# Relay-Switch.net
KiCad netlist of a schematic drawn in Altium Designer
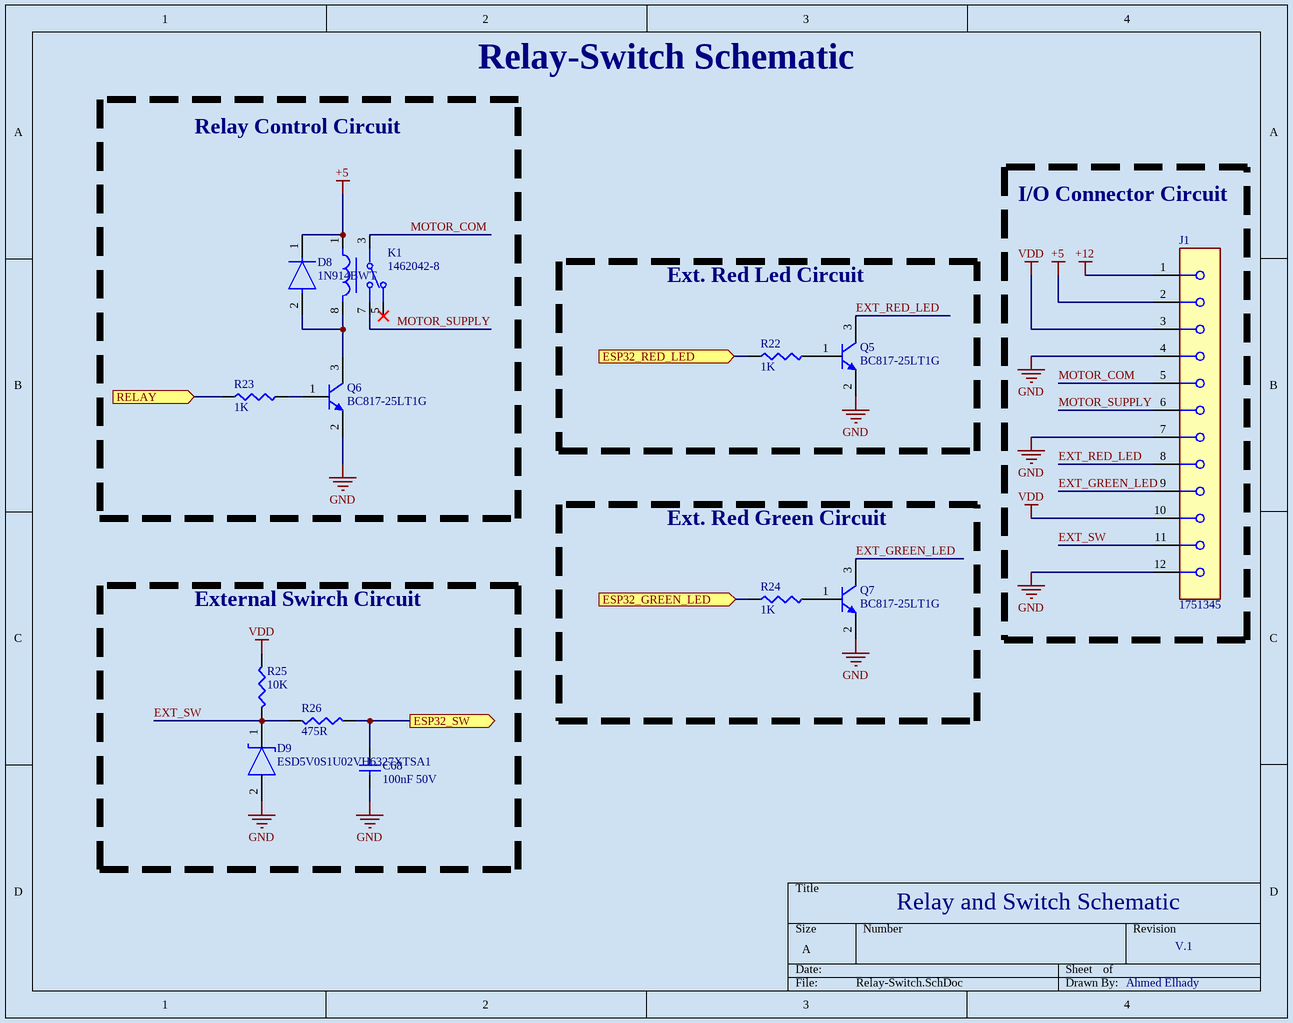
[diagram p0: Relay-Switch.SchDoc]

(export (version "E")
  (design (tool "Eeschema 10.0.6"))
  (components
    (comp (ref "C68")
      (value "100nF 50V")
      (footprint "0603 (1608 Metric)-CAP-100NF-50V")
      (description "0.1 µF ±10% 50V Ceramic Capacitor X7R 0603 (1608 Metric)")
      (fields
        (field (name "MANUFACTURER") "TDK")
        (field (name "MANUFACTURER PART NUMBER") "CGA3E2X7R1H104K080AA")
      )
      (libsource (lib "Sch for NFC") (part "CGA3E2X7R1H104K080AA"))
    )
    (comp (ref "D8")
      (value "1N914BWT")
      (footprint "1N914BWT_dIODE_smd_ON_Semiconductor_502-01_MFG")
      (description "Diode 75 V 200mA Surface Mount SOD-523F")
      (fields (field (name "MANUFACTURER") "onsemi"))
      (libsource (lib "Sch for NFC") (part "1N914BWT"))
    )
    (comp (ref "D9")
      (value "ESD5V0S1U02VH6327XTSA1")
      (footprint "tvs_diode_Infineon_PG-SC79-2_MFG")
      (description "14.5V (Typ) Clamp 5.5A (8/20µs) Ipp Tvs Diode Surface Mount PG-SC79-2-1")
      (fields (field (name "MANUFACTURER") "Infineon"))
      (libsource (lib "Sch for NFC") (part "ESD5V0S1U02VH6327XTSA1"))
    )
    (comp (ref "J1")
      (value "1751345")
      (footprint "Terminal_Block_12pin_screw_Phoenix_Contact_1751345_0")
      (description "12 Position Wire to Board Terminal Block Horizontal with Board 0.138\" (3.50mm) Through Hole")
      (fields (field (name "MANUFACTURER") "Phoenix Contact") (field (name "VOLTAGE") "300V"))
      (libsource (lib "Sch for NFC") (part "1751345"))
    )
    (comp (ref "K1")
      (value "1462042-8")
      (footprint "RELAY_SPDT_TE_1462042-8_0")
      (description "Telecom Relay SPDT (1 Form C) Surface Mount")
      (fields (field (name "MANUFACTURER") "TE Connectivity"))
      (libsource (lib "Sch for NFC") (part "1462042-8"))
    )
    (comp (ref "Q5")
      (value "BC817-25LT1G")
      (footprint "transitor_npn_ONSC-SOT-23-3-318-08_V")
      (description "Bipolar (BJT) Transistor NPN 45 V 500 mA 100MHz 300 mW Surface Mount SOT-23-3 (TO-236)")
      (fields (field (name "MANUFACTURER") "onsemi"))
      (libsource (lib "Sch for NFC") (part "BC817-25LT1G"))
    )
    (comp (ref "Q6")
      (value "BC817-25LT1G")
      (footprint "transitor_npn_ONSC-SOT-23-3-318-08_V")
      (description "Bipolar (BJT) Transistor NPN 45 V 500 mA 100MHz 300 mW Surface Mount SOT-23-3 (TO-236)")
      (fields (field (name "MANUFACTURER") "onsemi"))
      (libsource (lib "Sch for NFC") (part "BC817-25LT1G"))
    )
    (comp (ref "Q7")
      (value "BC817-25LT1G")
      (footprint "transitor_npn_ONSC-SOT-23-3-318-08_V")
      (description "Bipolar (BJT) Transistor NPN 45 V 500 mA 100MHz 300 mW Surface Mount SOT-23-3 (TO-236)")
      (fields (field (name "MANUFACTURER") "onsemi"))
      (libsource (lib "Sch for NFC") (part "BC817-25LT1G"))
    )
    (comp (ref "R22")
      (value "1K")
      (footprint "1K_0603_KOA_Speer_RK73B1J_MFG")
      (description "1 kOhms ±5% 0.125W, 1/8W Chip Resistor 0603 (1608 Metric) Automotive AEC-Q200 Thick Film")
      (libsource (lib "Sch for NFC") (part "RK73B1JTTD102J"))
    )
    (comp (ref "R23")
      (value "1K")
      (footprint "1K_0603_KOA_Speer_RK73B1J_MFG")
      (description "1 kOhms ±5% 0.125W, 1/8W Chip Resistor 0603 (1608 Metric) Automotive AEC-Q200 Thick Film")
      (libsource (lib "Sch for NFC") (part "RK73B1JTTD102J"))
    )
    (comp (ref "R24")
      (value "1K")
      (footprint "1K_0603_KOA_Speer_RK73B1J_MFG")
      (description "1 kOhms ±5% 0.125W, 1/8W Chip Resistor 0603 (1608 Metric) Automotive AEC-Q200 Thick Film")
      (libsource (lib "Sch for NFC") (part "RK73B1JTTD102J"))
    )
    (comp (ref "R25")
      (value "10K")
      (footprint "YAGEO-0603-10K-0.1W")
      (description "10 kOhms ±1% 0.1W, 1/10W Chip Resistor 0603 (1608 Metric) Moisture Resistant Thick Film")
      (fields
        (field (name "MANUFACTURER") "Yageo Group")
        (field (name "MANUFACTURER PART NUMBER") "RC0603FR-0710KL")
      )
      (libsource (lib "Sch for NFC") (part "RC0603FR-0710KL"))
    )
    (comp (ref "R26")
      (value "475R")
      (footprint "475R_0603_Panasonic_ERJ3EK_MFG")
      (description "475 Ohms ±1% 0.1W, 1/10W Chip Resistor 0603 (1608 Metric) Automotive AEC-Q200 Thick Film")
      (fields
        (field (name "MANUFACTURER") "Panasonic")
        (field (name "MANUFACTURER PART NUMBER") "ERJ-3EKF4750V")
      )
      (libsource (lib "Sch for NFC") (part "ERJ-3EKF4750V"))
    )
  )
  (nets
    (net (code "1") (name "+5") (class "Default")
      (node (ref "D8") (pin "1") (pinfunction "CATHODE_1") (pintype "passive"))
      (node (ref "J1") (pin "2") (pinfunction "2_2") (pintype "passive"))
      (node (ref "K1") (pin "1") (pinfunction "1_1") (pintype "passive"))
    )
    (net (code "2") (name "+12") (class "Default")
      (node (ref "J1") (pin "1") (pinfunction "1_1") (pintype "passive"))
    )
    (net (code "3") (name "/ESP32_GREEN_LED") (class "Default")
      (node (ref "R24") (pin "2") (pinfunction "2_2") (pintype "passive"))
    )
    (net (code "4") (name "/ESP32_RED_LED") (class "Default")
      (node (ref "R22") (pin "2") (pinfunction "2_2") (pintype "passive"))
    )
    (net (code "5") (name "/ESP32_SW") (class "Default")
      (node (ref "C68") (pin "2") (pinfunction "2_2") (pintype "passive"))
      (node (ref "R26") (pin "2") (pinfunction "2_2") (pintype "passive"))
    )
    (net (code "6") (name "/EXT_GREEN_LED") (class "Default")
      (node (ref "J1") (pin "9") (pinfunction "9_9") (pintype "passive"))
      (node (ref "Q7") (pin "3") (pinfunction "C_3") (pintype "passive"))
    )
    (net (code "7") (name "/EXT_RED_LED") (class "Default")
      (node (ref "J1") (pin "8") (pinfunction "8_8") (pintype "passive"))
      (node (ref "Q5") (pin "3") (pinfunction "C_3") (pintype "passive"))
    )
    (net (code "8") (name "/EXT_SW") (class "Default")
      (node (ref "D9") (pin "1") (pinfunction "CATHODE_1") (pintype "passive"))
      (node (ref "J1") (pin "11") (pinfunction "11_11") (pintype "passive"))
      (node (ref "R25") (pin "1") (pinfunction "1_1") (pintype "passive"))
      (node (ref "R26") (pin "1") (pinfunction "1_1") (pintype "passive"))
    )
    (net (code "9") (name "/MOTOR_COM") (class "Default")
      (node (ref "J1") (pin "5") (pinfunction "5_5") (pintype "passive"))
      (node (ref "K1") (pin "3") (pinfunction "3_3") (pintype "passive"))
    )
    (net (code "10") (name "/MOTOR_SUPPLY") (class "Default")
      (node (ref "J1") (pin "6") (pinfunction "6_6") (pintype "passive"))
      (node (ref "K1") (pin "7") (pinfunction "7_7") (pintype "passive"))
    )
    (net (code "11") (name "/RELAY") (class "Default")
      (node (ref "R23") (pin "2") (pinfunction "2_2") (pintype "passive"))
    )
    (net (code "12") (name "GND") (class "Default")
      (node (ref "C68") (pin "1") (pinfunction "1_1") (pintype "passive"))
      (node (ref "D9") (pin "2") (pinfunction "ANODE_2") (pintype "passive"))
      (node (ref "J1") (pin "12") (pinfunction "12_12") (pintype "passive"))
      (node (ref "J1") (pin "4") (pinfunction "4_4") (pintype "passive"))
      (node (ref "J1") (pin "7") (pinfunction "7_7") (pintype "passive"))
      (node (ref "Q5") (pin "2") (pinfunction "E_2") (pintype "passive"))
      (node (ref "Q6") (pin "2") (pinfunction "E_2") (pintype "passive"))
      (node (ref "Q7") (pin "2") (pinfunction "E_2") (pintype "passive"))
    )
    (net (code "13") (name "Net-(D8-ANODE)") (class "Default")
      (node (ref "D8") (pin "2") (pinfunction "ANODE_2") (pintype "passive"))
      (node (ref "K1") (pin "8") (pinfunction "8_8") (pintype "passive"))
      (node (ref "Q6") (pin "3") (pinfunction "C_3") (pintype "passive"))
    )
    (net (code "14") (name "Net-(Q5-B)") (class "Default")
      (node (ref "Q5") (pin "1") (pinfunction "B_1") (pintype "passive"))
      (node (ref "R22") (pin "1") (pinfunction "1_1") (pintype "passive"))
    )
    (net (code "15") (name "Net-(Q6-B)") (class "Default")
      (node (ref "Q6") (pin "1") (pinfunction "B_1") (pintype "passive"))
      (node (ref "R23") (pin "1") (pinfunction "1_1") (pintype "passive"))
    )
    (net (code "16") (name "Net-(Q7-B)") (class "Default")
      (node (ref "Q7") (pin "1") (pinfunction "B_1") (pintype "passive"))
      (node (ref "R24") (pin "1") (pinfunction "1_1") (pintype "passive"))
    )
    (net (code "17") (name "VDD") (class "Default")
      (node (ref "J1") (pin "10") (pinfunction "10_10") (pintype "passive"))
      (node (ref "J1") (pin "3") (pinfunction "3_3") (pintype "passive"))
      (node (ref "R25") (pin "2") (pinfunction "2_2") (pintype "passive"))
    )
    (net (code "18") (name "unconnected-(K1-Pad5)") (class "Default")
      (node (ref "K1") (pin "5") (pinfunction "5_5") (pintype "passive+no_connect"))
    )
  )
)
